# Battery_Interface.net
KiCad netlist of a schematic drawn in Altium Designer
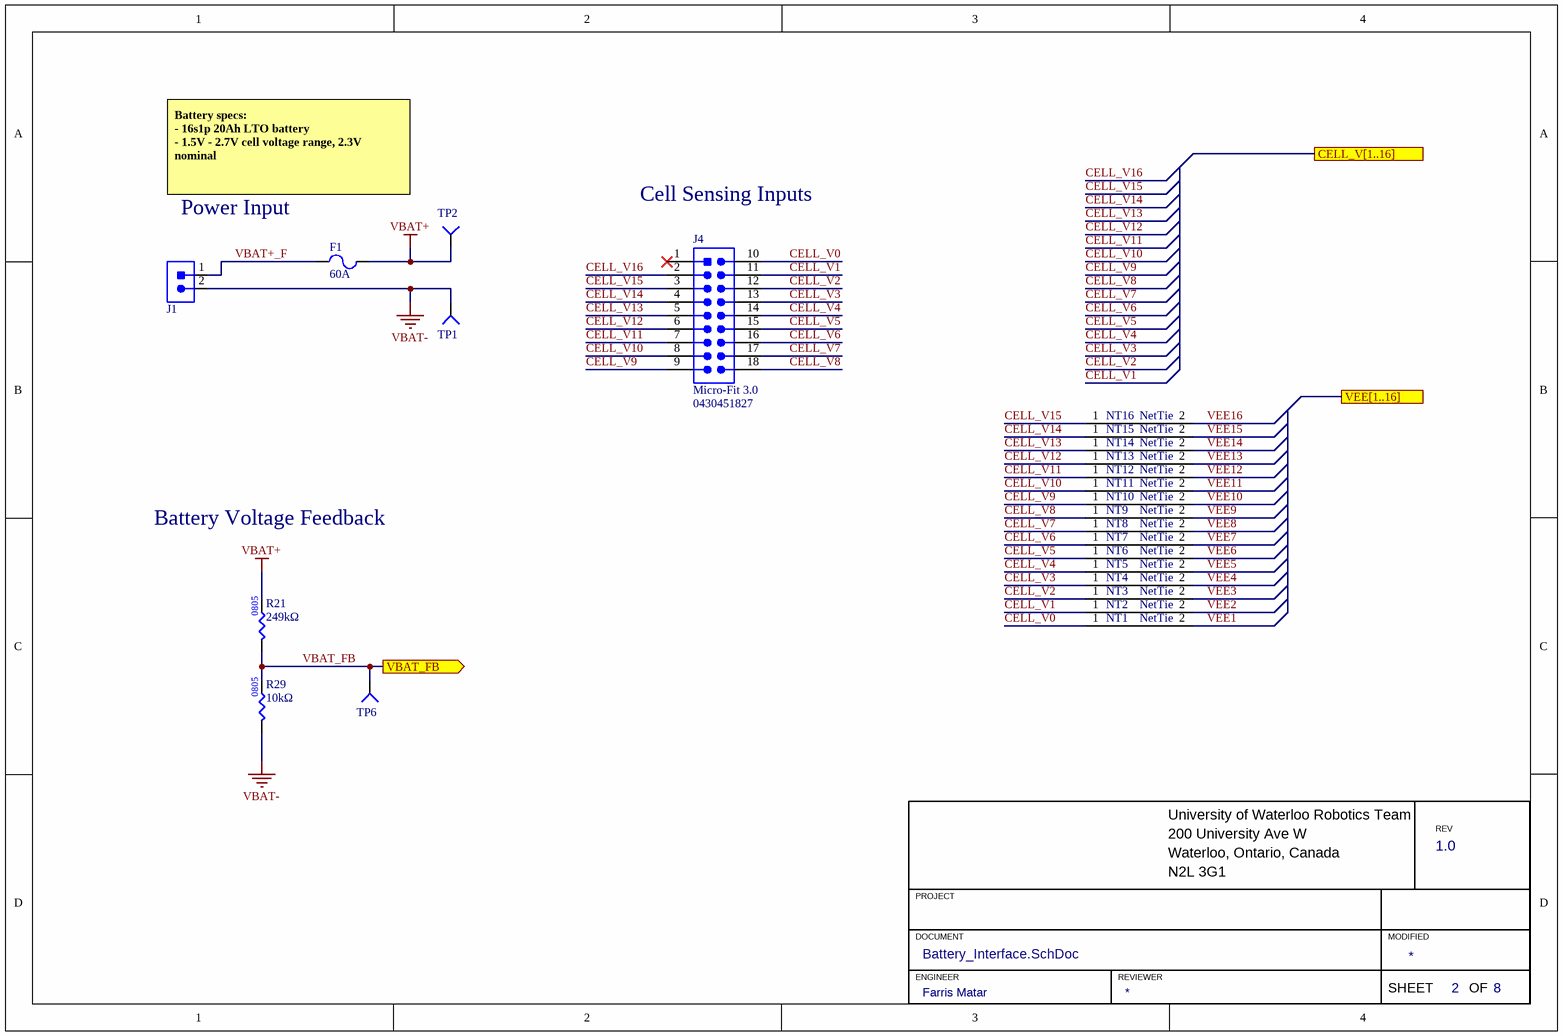
[diagram p0: Battery_Interface.SchDoc]

(export (version "E")
  (design (tool "Eeschema 10.0.6"))
  (components
    (comp (ref "F1")
      (value "FUSE_60A_3812")
      (footprint "FUSE_3812_BOURNS")
      (description "FUSE BRD 60A 250VAC 100VDC 2SMD")
      (fields (field (name "CURRENT RATING") "60A"))
      (libsource (lib "Personal_Schematic_Library_2022") (part "FUSE_60A_3812"))
    )
    (comp (ref "J1")
      (value "CON_2POS_XT90")
      (footprint "XT90")
      (description "HIGH QUALITY GOLD PLATED XT90 MA")
      (libsource (lib "Personal_Schematic_Library_2022") (part "CON_2POS_XT90"))
    )
    (comp (ref "J4")
      (value "0430451827")
      (footprint "MOLEX-0430451827")
      (description "CONN HEADER VERT 18POS 3MM")
      (fields
        (field (name "FAMILY") "Micro-Fit 3.0")
        (field (name "MANUFACTURER PART NUMBER 1") "0430451827")
      )
      (libsource (lib "Personal_Schematic_Library_2022") (part "CON_MOLEX-HDR_9x2_TH"))
    )
    (comp (ref "NT1")
      (value "NetTie")
      (footprint "NET_TIE")
      (libsource (lib "Personal_Schematic_Library_2022") (part "NetTie"))
    )
    (comp (ref "NT2")
      (value "NetTie")
      (footprint "NET_TIE")
      (libsource (lib "Personal_Schematic_Library_2022") (part "NetTie"))
    )
    (comp (ref "NT3")
      (value "NetTie")
      (footprint "NET_TIE")
      (libsource (lib "Personal_Schematic_Library_2022") (part "NetTie"))
    )
    (comp (ref "NT4")
      (value "NetTie")
      (footprint "NET_TIE")
      (libsource (lib "Personal_Schematic_Library_2022") (part "NetTie"))
    )
    (comp (ref "NT5")
      (value "NetTie")
      (footprint "NET_TIE")
      (libsource (lib "Personal_Schematic_Library_2022") (part "NetTie"))
    )
    (comp (ref "NT6")
      (value "NetTie")
      (footprint "NET_TIE")
      (libsource (lib "Personal_Schematic_Library_2022") (part "NetTie"))
    )
    (comp (ref "NT7")
      (value "NetTie")
      (footprint "NET_TIE")
      (libsource (lib "Personal_Schematic_Library_2022") (part "NetTie"))
    )
    (comp (ref "NT8")
      (value "NetTie")
      (footprint "NET_TIE")
      (libsource (lib "Personal_Schematic_Library_2022") (part "NetTie"))
    )
    (comp (ref "NT9")
      (value "NetTie")
      (footprint "NET_TIE")
      (libsource (lib "Personal_Schematic_Library_2022") (part "NetTie"))
    )
    (comp (ref "NT10")
      (value "NetTie")
      (footprint "NET_TIE")
      (libsource (lib "Personal_Schematic_Library_2022") (part "NetTie"))
    )
    (comp (ref "NT11")
      (value "NetTie")
      (footprint "NET_TIE")
      (libsource (lib "Personal_Schematic_Library_2022") (part "NetTie"))
    )
    (comp (ref "NT12")
      (value "NetTie")
      (footprint "NET_TIE")
      (libsource (lib "Personal_Schematic_Library_2022") (part "NetTie"))
    )
    (comp (ref "NT13")
      (value "NetTie")
      (footprint "NET_TIE")
      (libsource (lib "Personal_Schematic_Library_2022") (part "NetTie"))
    )
    (comp (ref "NT14")
      (value "NetTie")
      (footprint "NET_TIE")
      (libsource (lib "Personal_Schematic_Library_2022") (part "NetTie"))
    )
    (comp (ref "NT15")
      (value "NetTie")
      (footprint "NET_TIE")
      (libsource (lib "Personal_Schematic_Library_2022") (part "NetTie"))
    )
    (comp (ref "NT16")
      (value "NetTie")
      (footprint "NET_TIE")
      (libsource (lib "Personal_Schematic_Library_2022") (part "NetTie"))
    )
    (comp (ref "R21")
      (value "249kΩ")
      (footprint "RES0805")
      (description "RES 249K OHM 1% 1/8W 0805")
      (fields (field (name "LCSC PART #") "C25825") (field (name "Comment") "RES_249kΩ_0805_1%"))
      (libsource (lib "Personal_Schematic_Library_2022") (part "RES_249kΩ_0805_1%"))
    )
    (comp (ref "R29")
      (value "10kΩ")
      (footprint "RES0805")
      (description "RES 10K OHM 5% 1/8W 0805")
      (fields (field (name "LCSC PART #") "C17414") (field (name "Comment") "RES_10kΩ_0805_5%"))
      (libsource (lib "Personal_Schematic_Library_2022") (part "RES_10kΩ_0805_5%"))
    )
    (comp (ref "TP1")
      (value "TESTPOINT_SMD_LOOP")
      (footprint "S1751-46R")
      (description "TESTPOINT SMD LOOP")
      (libsource (lib "UWRT_Schematic_Library_2020") (part "TESTPOINT_SMD_LOOP"))
    )
    (comp (ref "TP2")
      (value "TESTPOINT_SMD_LOOP")
      (footprint "S1751-46R")
      (description "TESTPOINT SMD LOOP")
      (libsource (lib "UWRT_Schematic_Library_2020") (part "TESTPOINT_SMD_LOOP"))
    )
    (comp (ref "TP6")
      (value "TESTPOINT_1MM_CIRCLE")
      (footprint "TESTPOINT_CIRCLE_1MM")
      (description "TESTPOINT 1MM CIRCLE")
      (libsource (lib "Personal_Schematic_Library_2022") (part "TESTPOINT_1MM_CIRCLE"))
    )
  )
  (nets
    (net (code "1") (name "/CELL_V0") (class "Default")
      (node (ref "J4") (pin "10") (pinfunction "10_10") (pintype "passive"))
      (node (ref "NT1") (pin "1") (pinfunction "1_1") (pintype "passive"))
    )
    (net (code "2") (name "/CELL_V1") (class "Default")
      (node (ref "J4") (pin "11") (pinfunction "11_11") (pintype "passive"))
      (node (ref "NT2") (pin "1") (pinfunction "1_1") (pintype "passive"))
    )
    (net (code "3") (name "/CELL_V2") (class "Default")
      (node (ref "J4") (pin "12") (pinfunction "12_12") (pintype "passive"))
      (node (ref "NT3") (pin "1") (pinfunction "1_1") (pintype "passive"))
    )
    (net (code "4") (name "/CELL_V3") (class "Default")
      (node (ref "J4") (pin "13") (pinfunction "13_13") (pintype "passive"))
      (node (ref "NT4") (pin "1") (pinfunction "1_1") (pintype "passive"))
    )
    (net (code "5") (name "/CELL_V4") (class "Default")
      (node (ref "J4") (pin "14") (pinfunction "14_14") (pintype "passive"))
      (node (ref "NT5") (pin "1") (pinfunction "1_1") (pintype "passive"))
    )
    (net (code "6") (name "/CELL_V5") (class "Default")
      (node (ref "J4") (pin "15") (pinfunction "15_15") (pintype "passive"))
      (node (ref "NT6") (pin "1") (pinfunction "1_1") (pintype "passive"))
    )
    (net (code "7") (name "/CELL_V6") (class "Default")
      (node (ref "J4") (pin "16") (pinfunction "16_16") (pintype "passive"))
      (node (ref "NT7") (pin "1") (pinfunction "1_1") (pintype "passive"))
    )
    (net (code "8") (name "/CELL_V7") (class "Default")
      (node (ref "J4") (pin "17") (pinfunction "17_17") (pintype "passive"))
      (node (ref "NT8") (pin "1") (pinfunction "1_1") (pintype "passive"))
    )
    (net (code "9") (name "/CELL_V8") (class "Default")
      (node (ref "J4") (pin "18") (pinfunction "18_18") (pintype "passive"))
      (node (ref "NT9") (pin "1") (pinfunction "1_1") (pintype "passive"))
    )
    (net (code "10") (name "/CELL_V9") (class "Default")
      (node (ref "J4") (pin "9") (pinfunction "9_9") (pintype "passive"))
      (node (ref "NT10") (pin "1") (pinfunction "1_1") (pintype "passive"))
    )
    (net (code "11") (name "/CELL_V10") (class "Default")
      (node (ref "J4") (pin "8") (pinfunction "8_8") (pintype "passive"))
      (node (ref "NT11") (pin "1") (pinfunction "1_1") (pintype "passive"))
    )
    (net (code "12") (name "/CELL_V11") (class "Default")
      (node (ref "J4") (pin "7") (pinfunction "7_7") (pintype "passive"))
      (node (ref "NT12") (pin "1") (pinfunction "1_1") (pintype "passive"))
    )
    (net (code "13") (name "/CELL_V12") (class "Default")
      (node (ref "J4") (pin "6") (pinfunction "6_6") (pintype "passive"))
      (node (ref "NT13") (pin "1") (pinfunction "1_1") (pintype "passive"))
    )
    (net (code "14") (name "/CELL_V13") (class "Default")
      (node (ref "J4") (pin "5") (pinfunction "5_5") (pintype "passive"))
      (node (ref "NT14") (pin "1") (pinfunction "1_1") (pintype "passive"))
    )
    (net (code "15") (name "/CELL_V14") (class "Default")
      (node (ref "J4") (pin "4") (pinfunction "4_4") (pintype "passive"))
      (node (ref "NT15") (pin "1") (pinfunction "1_1") (pintype "passive"))
    )
    (net (code "16") (name "/CELL_V15") (class "Default")
      (node (ref "J4") (pin "3") (pinfunction "3_3") (pintype "passive"))
      (node (ref "NT16") (pin "1") (pinfunction "1_1") (pintype "passive"))
    )
    (net (code "17") (name "/CELL_V16") (class "Default")
      (node (ref "J4") (pin "2") (pinfunction "2_2") (pintype "passive"))
    )
    (net (code "19") (name "/VBAT+_F") (class "Default")
      (node (ref "F1") (pin "1") (pinfunction "1_1") (pintype "passive"))
      (node (ref "J1") (pin "1") (pinfunction "1_1") (pintype "passive"))
    )
    (net (code "20") (name "/VBAT_FB") (class "Default")
      (node (ref "R21") (pin "1") (pinfunction "1_1") (pintype "passive"))
      (node (ref "R29") (pin "2") (pinfunction "2_2") (pintype "passive"))
      (node (ref "TP6") (pin "1") (pinfunction "=value_1") (pintype "passive"))
    )
    (net (code "21") (name "/VEE1") (class "Default")
      (node (ref "NT1") (pin "2") (pinfunction "2_2") (pintype "passive"))
    )
    (net (code "22") (name "/VEE2") (class "Default")
      (node (ref "NT2") (pin "2") (pinfunction "2_2") (pintype "passive"))
    )
    (net (code "23") (name "/VEE3") (class "Default")
      (node (ref "NT3") (pin "2") (pinfunction "2_2") (pintype "passive"))
    )
    (net (code "24") (name "/VEE4") (class "Default")
      (node (ref "NT4") (pin "2") (pinfunction "2_2") (pintype "passive"))
    )
    (net (code "25") (name "/VEE5") (class "Default")
      (node (ref "NT5") (pin "2") (pinfunction "2_2") (pintype "passive"))
    )
    (net (code "26") (name "/VEE6") (class "Default")
      (node (ref "NT6") (pin "2") (pinfunction "2_2") (pintype "passive"))
    )
    (net (code "27") (name "/VEE7") (class "Default")
      (node (ref "NT7") (pin "2") (pinfunction "2_2") (pintype "passive"))
    )
    (net (code "28") (name "/VEE8") (class "Default")
      (node (ref "NT8") (pin "2") (pinfunction "2_2") (pintype "passive"))
    )
    (net (code "29") (name "/VEE9") (class "Default")
      (node (ref "NT9") (pin "2") (pinfunction "2_2") (pintype "passive"))
    )
    (net (code "30") (name "/VEE10") (class "Default")
      (node (ref "NT10") (pin "2") (pinfunction "2_2") (pintype "passive"))
    )
    (net (code "31") (name "/VEE11") (class "Default")
      (node (ref "NT11") (pin "2") (pinfunction "2_2") (pintype "passive"))
    )
    (net (code "32") (name "/VEE12") (class "Default")
      (node (ref "NT12") (pin "2") (pinfunction "2_2") (pintype "passive"))
    )
    (net (code "33") (name "/VEE13") (class "Default")
      (node (ref "NT13") (pin "2") (pinfunction "2_2") (pintype "passive"))
    )
    (net (code "34") (name "/VEE14") (class "Default")
      (node (ref "NT14") (pin "2") (pinfunction "2_2") (pintype "passive"))
    )
    (net (code "35") (name "/VEE15") (class "Default")
      (node (ref "NT15") (pin "2") (pinfunction "2_2") (pintype "passive"))
    )
    (net (code "36") (name "/VEE16") (class "Default")
      (node (ref "NT16") (pin "2") (pinfunction "2_2") (pintype "passive"))
    )
    (net (code "38") (name "VBAT+") (class "Default")
      (node (ref "F1") (pin "2") (pinfunction "2_2") (pintype "passive"))
      (node (ref "R21") (pin "2") (pinfunction "2_2") (pintype "passive"))
      (node (ref "TP2") (pin "1") (pinfunction "=value_1") (pintype "passive"))
    )
    (net (code "39") (name "VBAT-") (class "Default")
      (node (ref "J1") (pin "2") (pinfunction "2_2") (pintype "passive"))
      (node (ref "R29") (pin "1") (pinfunction "1_1") (pintype "passive"))
      (node (ref "TP1") (pin "1") (pinfunction "=value_1") (pintype "passive"))
    )
    (net (code "40") (name "unconnected-(J4-Pad1)") (class "Default")
      (node (ref "J4") (pin "1") (pinfunction "1_1") (pintype "passive+no_connect"))
    )
  )
)
